# Display_OLED.net
KiCad netlist of a schematic drawn in Altium Designer
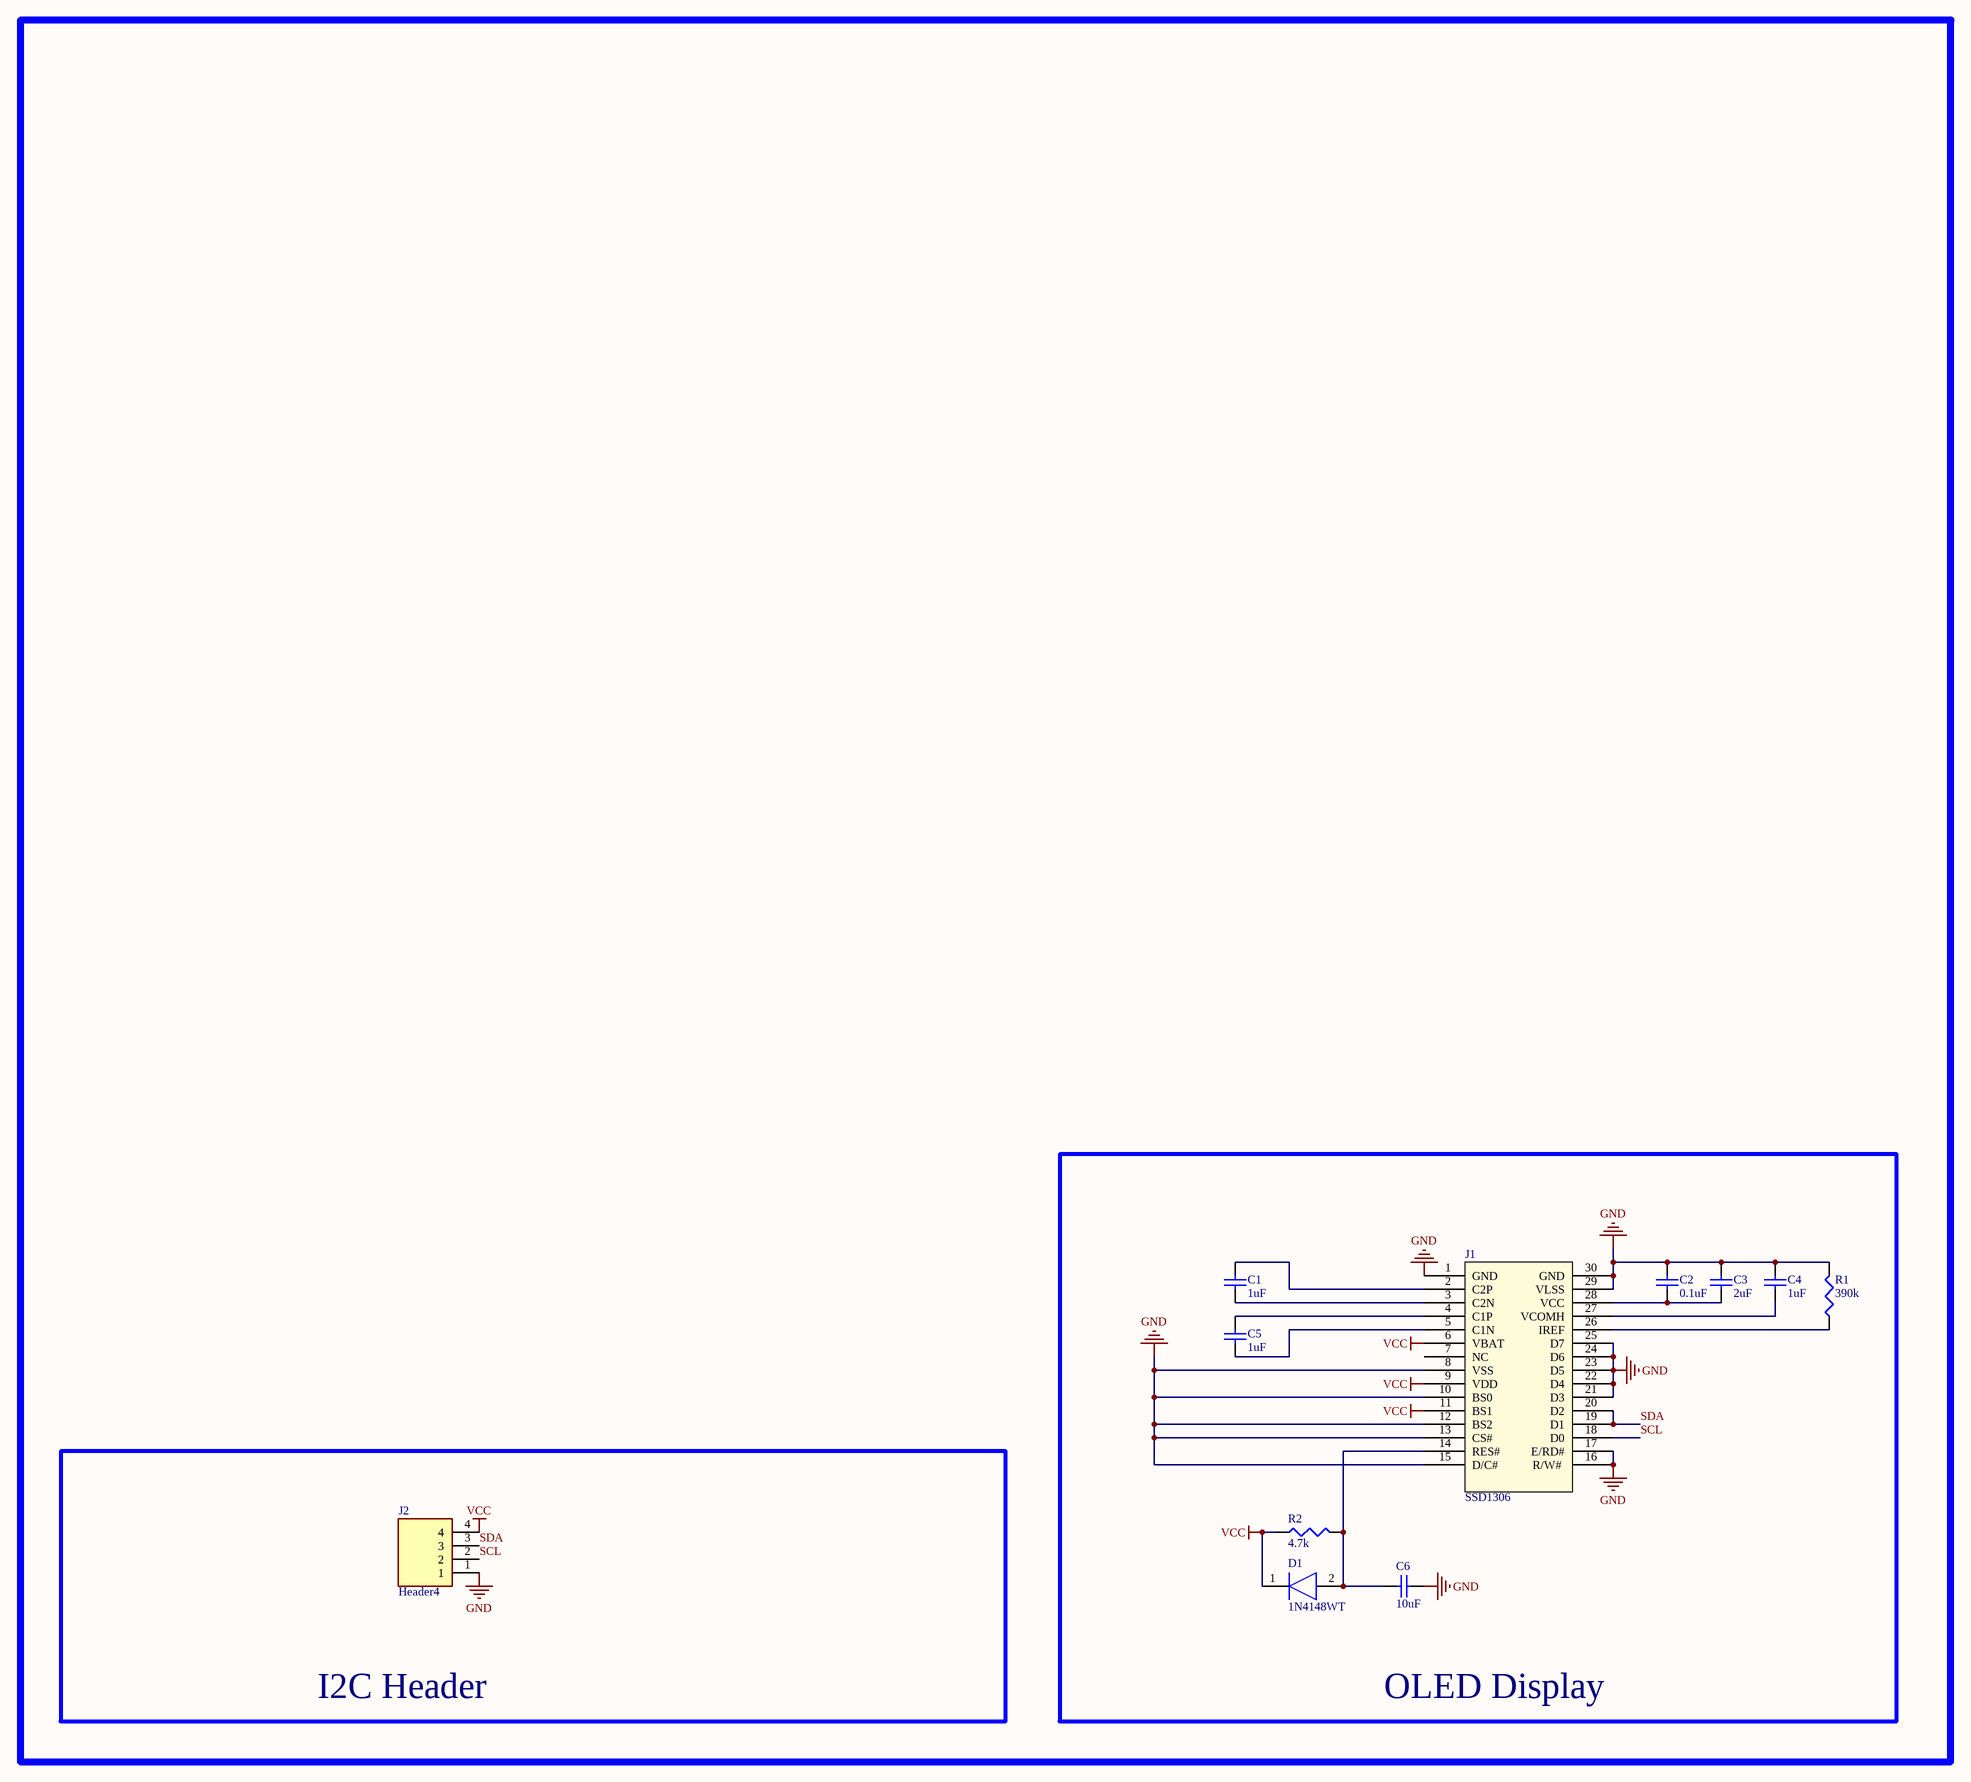
[diagram p0: Display_OLED.SchDoc]

(export (version "E")
  (design (tool "Eeschema 10.0.6"))
  (components
    (comp (ref "C1")
      (value "1uF")
      (footprint "0603")
      (description "Capacitor")
      (fields (field (name "PUBLISHER") "Altium Limited"))
      (libsource (lib "Display_Router") (part "Cap"))
    )
    (comp (ref "C2")
      (value "0.1uF")
      (footprint "0603")
      (description "Capacitor")
      (fields (field (name "PUBLISHER") "Altium Limited"))
      (libsource (lib "Display_Router") (part "Cap"))
    )
    (comp (ref "C3")
      (value "2uF")
      (footprint "0603")
      (description "Capacitor")
      (fields (field (name "PUBLISHER") "Altium Limited"))
      (libsource (lib "Display_Router") (part "Cap"))
    )
    (comp (ref "C4")
      (value "1uF")
      (footprint "0603")
      (description "Capacitor")
      (fields (field (name "PUBLISHER") "Altium Limited"))
      (libsource (lib "Display_Router") (part "Cap"))
    )
    (comp (ref "C5")
      (value "1uF")
      (footprint "0603")
      (description "Capacitor")
      (fields (field (name "PUBLISHER") "Altium Limited"))
      (libsource (lib "Display_Router") (part "Cap"))
    )
    (comp (ref "C6")
      (value "10uF")
      (footprint "0603")
      (description "Capacitor")
      (fields (field (name "PUBLISHER") "Altium Limited"))
      (libsource (lib "Display_Router") (part "Cap"))
    )
    (comp (ref "D1")
      (value "1N4148WT")
      (footprint "SODFL1608X70N")
      (description "Diode")
      (libsource (lib "Display_Router") (part "1N4148WT"))
    )
    (comp (ref "J1")
      (value "SSD1306")
      (footprint "Header30")
      (libsource (lib "Display_Router") (part "Header_SMD_30"))
    )
    (comp (ref "J2")
      (value "Header4")
      (footprint "HDRV4W165P0X396_1X4_1508X1020X1425P")
      (description "Connector")
      (fields (field (name "MANUFACTURER_PART_NUMBER") "0009652048"))
      (libsource (lib "Display_Router") (part "Header4"))
    )
    (comp (ref "R1")
      (value "390k")
      (footprint "0603")
      (description "Resistor")
      (fields (field (name "PUBLISHER") "Altium Limited"))
      (libsource (lib "Display_Router") (part "Res"))
    )
    (comp (ref "R2")
      (value "4.7k")
      (footprint "0603")
      (description "Resistor")
      (fields (field (name "PUBLISHER") "Altium Limited"))
      (libsource (lib "Display_Router") (part "Res"))
    )
  )
  (nets
    (net (code "1") (name "/SCL") (class "Default")
      (node (ref "J1") (pin "18") (pinfunction "D0_18") (pintype "passive"))
      (node (ref "J2") (pin "2") (pinfunction "2_2") (pintype "passive"))
    )
    (net (code "2") (name "/SDA") (class "Default")
      (node (ref "J1") (pin "19") (pinfunction "D1_19") (pintype "passive"))
      (node (ref "J1") (pin "20") (pinfunction "D2_20") (pintype "passive"))
      (node (ref "J2") (pin "3") (pinfunction "3_3") (pintype "passive"))
    )
    (net (code "3") (name "GND") (class "Default")
      (node (ref "C2") (pin "1") (pinfunction "1_1") (pintype "passive"))
      (node (ref "C3") (pin "1") (pinfunction "1_1") (pintype "passive"))
      (node (ref "C4") (pin "1") (pinfunction "1_1") (pintype "passive"))
      (node (ref "C6") (pin "2") (pinfunction "2_2") (pintype "passive"))
      (node (ref "J1") (pin "1") (pinfunction "GND_1") (pintype "passive"))
      (node (ref "J1") (pin "10") (pinfunction "BS0_10") (pintype "passive"))
      (node (ref "J1") (pin "12") (pinfunction "BS2_12") (pintype "passive"))
      (node (ref "J1") (pin "13") (pinfunction "CS#_13") (pintype "passive"))
      (node (ref "J1") (pin "15") (pinfunction "D/C#_15") (pintype "passive"))
      (node (ref "J1") (pin "16") (pinfunction "R/W#_16") (pintype "passive"))
      (node (ref "J1") (pin "17") (pinfunction "E/RD#_17") (pintype "passive"))
      (node (ref "J1") (pin "21") (pinfunction "D3_21") (pintype "passive"))
      (node (ref "J1") (pin "22") (pinfunction "D4_22") (pintype "passive"))
      (node (ref "J1") (pin "23") (pinfunction "D5_23") (pintype "passive"))
      (node (ref "J1") (pin "24") (pinfunction "D6_24") (pintype "passive"))
      (node (ref "J1") (pin "25") (pinfunction "D7_25") (pintype "passive"))
      (node (ref "J1") (pin "29") (pinfunction "VLSS_29") (pintype "passive"))
      (node (ref "J1") (pin "30") (pinfunction "GND_30") (pintype "passive"))
      (node (ref "J1") (pin "8") (pinfunction "VSS_8") (pintype "passive"))
      (node (ref "J2") (pin "1") (pinfunction "1_1") (pintype "passive"))
      (node (ref "R1") (pin "2") (pinfunction "2_2") (pintype "passive"))
    )
    (net (code "4") (name "Net-(D1-A)") (class "Default")
      (node (ref "C6") (pin "1") (pinfunction "1_1") (pintype "passive"))
      (node (ref "D1") (pin "2") (pinfunction "A_2") (pintype "passive"))
      (node (ref "J1") (pin "14") (pinfunction "RES#_14") (pintype "passive"))
      (node (ref "R2") (pin "2") (pinfunction "2_2") (pintype "passive"))
    )
    (net (code "5") (name "Net-(J1-C1N)") (class "Default")
      (node (ref "C5") (pin "2") (pinfunction "2_2") (pintype "passive"))
      (node (ref "J1") (pin "5") (pinfunction "C1N_5") (pintype "passive"))
    )
    (net (code "6") (name "Net-(J1-C1P)") (class "Default")
      (node (ref "C5") (pin "1") (pinfunction "1_1") (pintype "passive"))
      (node (ref "J1") (pin "4") (pinfunction "C1P_4") (pintype "passive"))
    )
    (net (code "7") (name "Net-(J1-C2N)") (class "Default")
      (node (ref "C1") (pin "2") (pinfunction "2_2") (pintype "passive"))
      (node (ref "J1") (pin "3") (pinfunction "C2N_3") (pintype "passive"))
    )
    (net (code "8") (name "Net-(J1-C2P)") (class "Default")
      (node (ref "C1") (pin "1") (pinfunction "1_1") (pintype "passive"))
      (node (ref "J1") (pin "2") (pinfunction "C2P_2") (pintype "passive"))
    )
    (net (code "9") (name "Net-(J1-IREF)") (class "Default")
      (node (ref "J1") (pin "26") (pinfunction "IREF_26") (pintype "passive"))
      (node (ref "R1") (pin "1") (pinfunction "1_1") (pintype "passive"))
    )
    (net (code "10") (name "Net-(J1-VCC)") (class "Default")
      (node (ref "C2") (pin "2") (pinfunction "2_2") (pintype "passive"))
      (node (ref "C3") (pin "2") (pinfunction "2_2") (pintype "passive"))
      (node (ref "J1") (pin "28") (pinfunction "VCC_28") (pintype "passive"))
    )
    (net (code "11") (name "Net-(J1-VCOMH)") (class "Default")
      (node (ref "C4") (pin "2") (pinfunction "2_2") (pintype "passive"))
      (node (ref "J1") (pin "27") (pinfunction "VCOMH_27") (pintype "passive"))
    )
    (net (code "12") (name "VCC") (class "Default")
      (node (ref "D1") (pin "1") (pinfunction "K_1") (pintype "passive"))
      (node (ref "J1") (pin "11") (pinfunction "BS1_11") (pintype "passive"))
      (node (ref "J1") (pin "6") (pinfunction "VBAT_6") (pintype "passive"))
      (node (ref "J1") (pin "9") (pinfunction "VDD_9") (pintype "passive"))
      (node (ref "J2") (pin "4") (pinfunction "4_4") (pintype "passive"))
      (node (ref "R2") (pin "1") (pinfunction "1_1") (pintype "passive"))
    )
    (net (code "13") (name "unconnected-(J1-NC-Pad7)") (class "Default")
      (node (ref "J1") (pin "7") (pinfunction "NC_7") (pintype "passive"))
    )
  )
)
